# RTC_SEC.net
KiCad netlist of a schematic drawn in Altium Designer
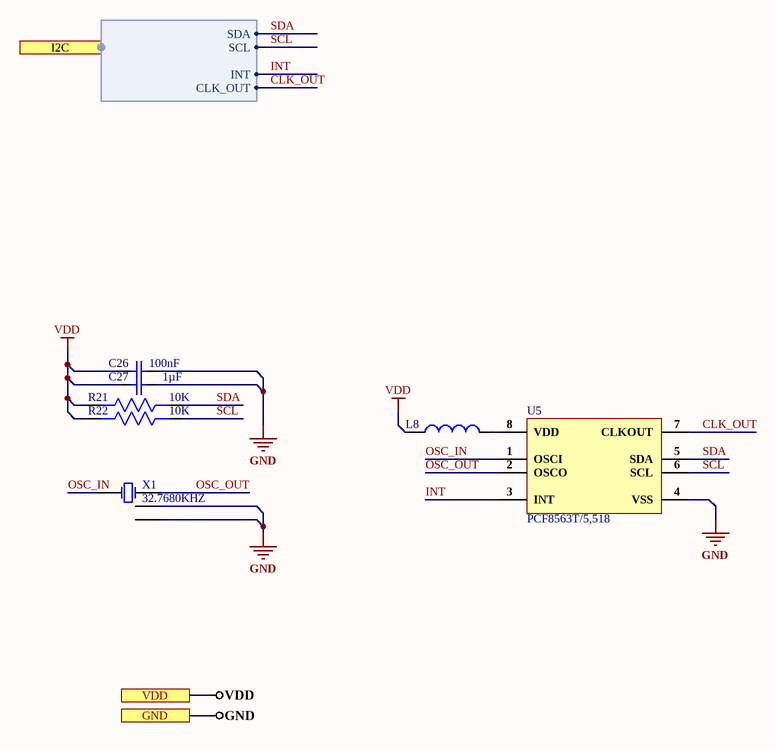
[diagram p0: RTC_SEC.SchDoc]

(export (version "E")
  (design (tool "Eeschema 10.0.6"))
  (components
    (comp (ref "C26")
      (value "100nF")
      (footprint "Cap0402")
      (description "CAP CER 0.1UF 25V X7R 0402")
      (fields
        (field (name "MANUFACTURER") "Yageo")
        (field (name "MANUFACTURER PART NUMBER") "CC0402KRX7R8BB104")
      )
      (libsource (lib "TT_IntLib") (part "CC0402KRX7R8BB104"))
    )
    (comp (ref "C27")
      (value "1µF")
      (footprint "Cap0402")
      (description "CAP CER 1UF 25V X5R 0402")
      (fields
        (field (name "MANUFACTURER") "Murata")
        (field (name "MANUFACTURER PART NUMBER") "GRM155R61E105KA12D")
      )
      (libsource (lib "TT_IntLib") (part "GRM155R61E105KA12D"))
    )
    (comp (ref "L8")
      (value "MMZ0603S601CT000")
      (footprint "IND 0201")
      (description "FERRITE BEAD 600 OHM 0201 1LN")
      (fields (field (name "MANUFACTURER") "TDK") (field (name "TOLERANCE") "25%"))
      (libsource (lib "TT_IntLib") (part "MMZ0603S601CT000"))
    )
    (comp (ref "R21")
      (value "10K")
      (footprint "Res-0201")
      (description "RES SMD 10K OHM 1% 1/20W 0201")
      (fields
        (field (name "MANUFACTURER") "Yageo")
        (field (name "MANUFACTURER PART NUMBER") "RC0201FR-0710KL")
      )
      (libsource (lib "TT_IntLib") (part "RC0201FR-0710KL"))
    )
    (comp (ref "R22")
      (value "10K")
      (footprint "Res-0201")
      (description "RES SMD 10K OHM 1% 1/20W 0201")
      (fields
        (field (name "MANUFACTURER") "Yageo")
        (field (name "MANUFACTURER PART NUMBER") "RC0201FR-0710KL")
      )
      (libsource (lib "TT_IntLib") (part "RC0201FR-0710KL"))
    )
    (comp (ref "U5")
      (value "PCF8563T/5,518")
      (footprint "8-SO")
      (description "IC RTC CLK/CALENDAR I2C 8-SOIC")
      (libsource (lib "TT_IntLib") (part "PCF8563T/5,518"))
    )
    (comp (ref "X1")
      (value "32.7680KHZ")
      (footprint "CM200C32768DZFT")
      (description "CRYSTAL 32.7680KHZ 12.5PF SMD")
      (fields
        (field (name "MANUFACTURER") "Citizen")
        (field (name "MANUFACTURER PART NUMBER") "CM200C32768DZFT")
      )
      (libsource (lib "TT_IntLib") (part "CM200C32768DZFT"))
    )
  )
  (nets
    (net (code "2") (name "/CLK_OUT") (class "Default")
      (node (ref "U5") (pin "7") (pinfunction "CLKOUT_7") (pintype "passive"))
    )
    (net (code "3") (name "/INT") (class "Default")
      (node (ref "U5") (pin "3") (pinfunction "INT_3") (pintype "passive"))
    )
    (net (code "4") (name "/OSC_IN") (class "Default")
      (node (ref "U5") (pin "1") (pinfunction "OSCI_1") (pintype "passive"))
      (node (ref "X1") (pin "1") (pinfunction "OSC1_1") (pintype "passive"))
    )
    (net (code "5") (name "/OSC_OUT") (class "Default")
      (node (ref "U5") (pin "2") (pinfunction "OSCO_2") (pintype "passive"))
      (node (ref "X1") (pin "4") (pinfunction "OSC2_4") (pintype "passive"))
    )
    (net (code "6") (name "/SCL") (class "Default")
      (node (ref "R22") (pin "1") (pintype "passive"))
      (node (ref "U5") (pin "6") (pinfunction "SCL_6") (pintype "passive"))
    )
    (net (code "7") (name "/SDA") (class "Default")
      (node (ref "R21") (pin "1") (pintype "passive"))
      (node (ref "U5") (pin "5") (pinfunction "SDA_5") (pintype "passive"))
    )
    (net (code "9") (name "GND") (class "Default")
      (node (ref "C26") (pin "1") (pintype "passive"))
      (node (ref "C27") (pin "1") (pintype "passive"))
      (node (ref "U5") (pin "4") (pinfunction "VSS_4") (pintype "passive"))
      (node (ref "X1") (pin "2") (pinfunction "OSC3_2") (pintype "passive"))
      (node (ref "X1") (pin "3") (pinfunction "OSC4_3") (pintype "passive"))
    )
    (net (code "10") (name "Net-(U5-VDD)") (class "Default")
      (node (ref "L8") (pin "2") (pinfunction "2_2") (pintype "passive"))
      (node (ref "U5") (pin "8") (pinfunction "VDD_8") (pintype "passive"))
    )
    (net (code "11") (name "VDD") (class "Default")
      (node (ref "C26") (pin "2") (pintype "passive"))
      (node (ref "C27") (pin "2") (pintype "passive"))
      (node (ref "L8") (pin "1") (pinfunction "1_1") (pintype "passive"))
      (node (ref "R21") (pin "2") (pintype "passive"))
      (node (ref "R22") (pin "2") (pintype "passive"))
    )
  )
)
